# IMU.net
KiCad netlist of a schematic drawn in Altium Designer
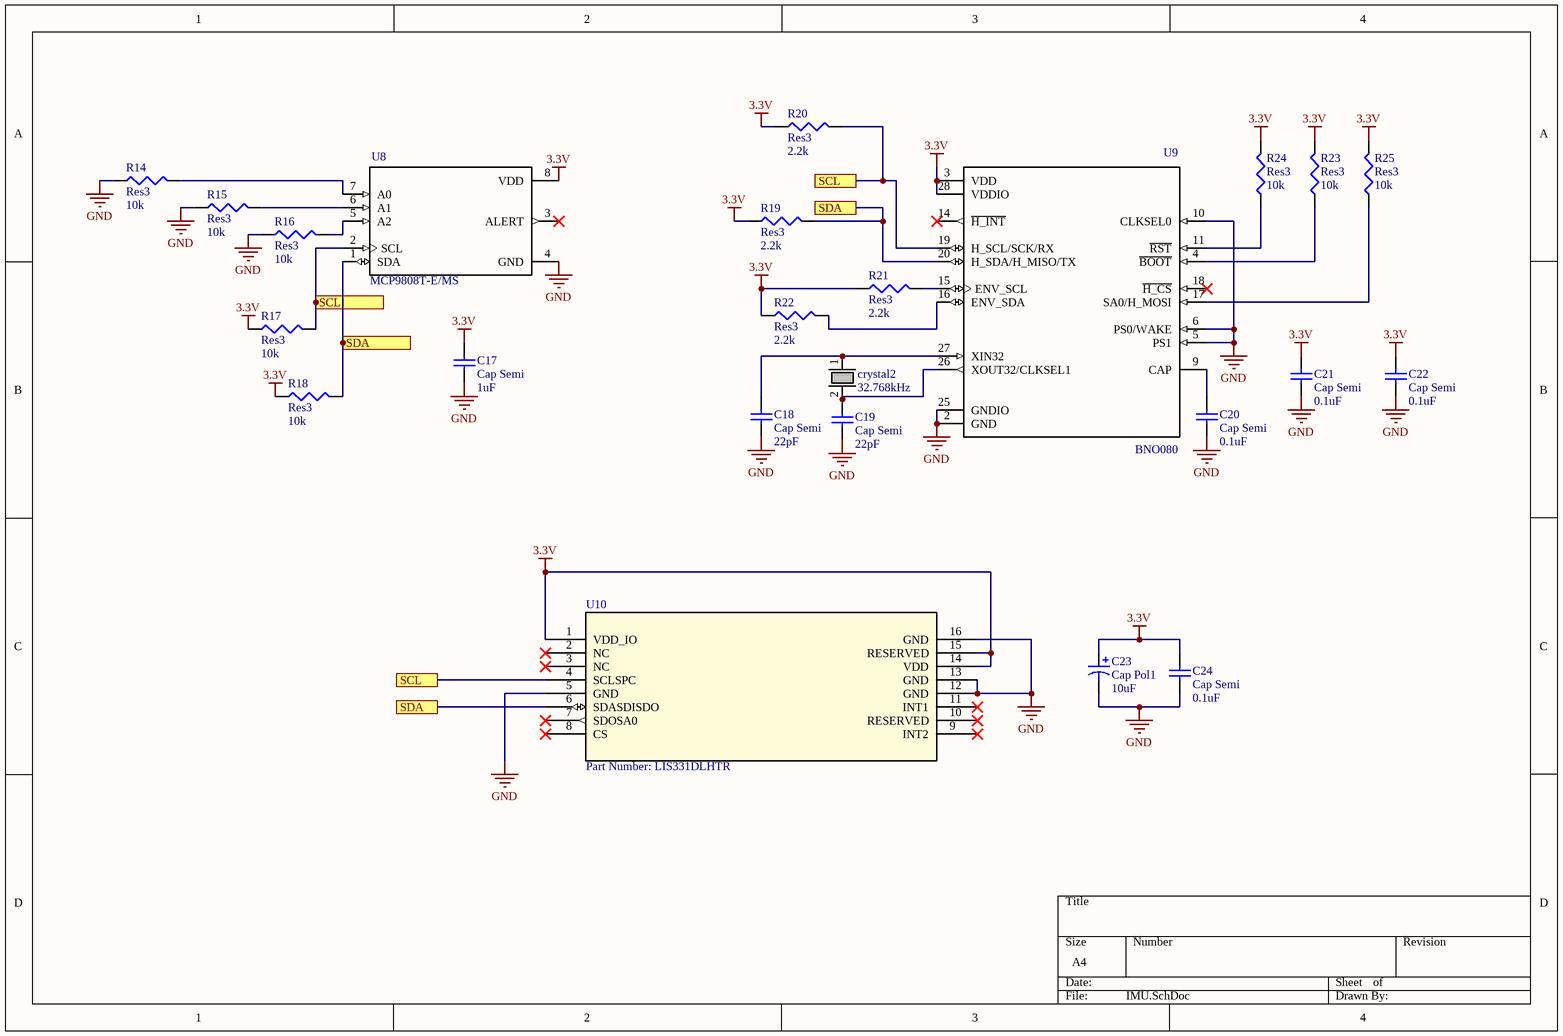
[diagram p0: IMU.SchDoc]

(export (version "E")
  (design (tool "Eeschema 10.0.6"))
  (components
    (comp (ref "C17")
      (value "Cap Semi")
      (footprint "C1206")
      (description "Capacitor (Semiconductor SIM Model)")
      (fields (field (name "ALTIUM_VALUE") "1uF") (field (name "PUBLISHER") "Altium Limited"))
      (libsource (lib "Miscellaneous Devices") (part "Cap Semi"))
    )
    (comp (ref "C18")
      (value "Cap Semi")
      (footprint "C1206")
      (description "Capacitor (Semiconductor SIM Model)")
      (fields (field (name "ALTIUM_VALUE") "22pF") (field (name "PUBLISHER") "Altium Limited"))
      (libsource (lib "Miscellaneous Devices") (part "Cap Semi"))
    )
    (comp (ref "C19")
      (value "Cap Semi")
      (footprint "C1206")
      (description "Capacitor (Semiconductor SIM Model)")
      (fields (field (name "ALTIUM_VALUE") "22pF") (field (name "PUBLISHER") "Altium Limited"))
      (libsource (lib "Miscellaneous Devices") (part "Cap Semi"))
    )
    (comp (ref "C20")
      (value "Cap Semi")
      (footprint "C1206")
      (description "Capacitor (Semiconductor SIM Model)")
      (fields (field (name "ALTIUM_VALUE") "0.1uF") (field (name "PUBLISHER") "Altium Limited"))
      (libsource (lib "Miscellaneous Devices") (part "Cap Semi"))
    )
    (comp (ref "C21")
      (value "Cap Semi")
      (footprint "C1206")
      (description "Capacitor (Semiconductor SIM Model)")
      (fields (field (name "ALTIUM_VALUE") "0.1uF") (field (name "PUBLISHER") "Altium Limited"))
      (libsource (lib "Miscellaneous Devices") (part "Cap Semi"))
    )
    (comp (ref "C22")
      (value "Cap Semi")
      (footprint "C1206")
      (description "Capacitor (Semiconductor SIM Model)")
      (fields (field (name "ALTIUM_VALUE") "0.1uF") (field (name "PUBLISHER") "Altium Limited"))
      (libsource (lib "Miscellaneous Devices") (part "Cap Semi"))
    )
    (comp (ref "C23")
      (value "Cap Pol1")
      (footprint "C1206")
      (description "Polarized Capacitor (Radial)")
      (fields (field (name "ALTIUM_VALUE") "10uF") (field (name "PUBLISHER") "Altium Limited"))
      (libsource (lib "Miscellaneous Devices") (part "Cap Pol1"))
    )
    (comp (ref "C24")
      (value "Cap Semi")
      (footprint "C1206")
      (description "Capacitor (Semiconductor SIM Model)")
      (fields (field (name "ALTIUM_VALUE") "0.1uF") (field (name "PUBLISHER") "Altium Limited"))
      (libsource (lib "Miscellaneous Devices") (part "Cap Semi"))
    )
    (comp (ref "crystal2")
      (value "32.768kHz")
      (footprint "ECS-.327-CDX-1128")
      (fields (field (name "Comment") "SMD_Crystal"))
      (libsource (lib "ECS-.327-CDX-1128") (part "ECS-.327-CDX-1128"))
    )
    (comp (ref "R14")
      (value "Res3")
      (footprint "6-0805_L")
      (description "Resistor")
      (fields (field (name "ALTIUM_VALUE") "10k") (field (name "PUBLISHER") "Altium Limited"))
      (libsource (lib "Miscellaneous Devices") (part "Res3"))
    )
    (comp (ref "R15")
      (value "Res3")
      (footprint "6-0805_L")
      (description "Resistor")
      (fields (field (name "ALTIUM_VALUE") "10k") (field (name "PUBLISHER") "Altium Limited"))
      (libsource (lib "Miscellaneous Devices") (part "Res3"))
    )
    (comp (ref "R16")
      (value "Res3")
      (footprint "6-0805_L")
      (description "Resistor")
      (fields (field (name "ALTIUM_VALUE") "10k") (field (name "PUBLISHER") "Altium Limited"))
      (libsource (lib "Miscellaneous Devices") (part "Res3"))
    )
    (comp (ref "R17")
      (value "Res3")
      (footprint "6-0805_L")
      (description "Resistor")
      (fields (field (name "ALTIUM_VALUE") "10k") (field (name "PUBLISHER") "Altium Limited"))
      (libsource (lib "Miscellaneous Devices") (part "Res3"))
    )
    (comp (ref "R18")
      (value "Res3")
      (footprint "6-0805_L")
      (description "Resistor")
      (fields (field (name "ALTIUM_VALUE") "10k") (field (name "PUBLISHER") "Altium Limited"))
      (libsource (lib "Miscellaneous Devices") (part "Res3"))
    )
    (comp (ref "R19")
      (value "Res3")
      (footprint "6-0805_L")
      (description "Resistor")
      (fields (field (name "ALTIUM_VALUE") "2.2k") (field (name "PUBLISHER") "Altium Limited"))
      (libsource (lib "Miscellaneous Devices") (part "Res3"))
    )
    (comp (ref "R20")
      (value "Res3")
      (footprint "6-0805_L")
      (description "Resistor")
      (fields (field (name "ALTIUM_VALUE") "2.2k") (field (name "PUBLISHER") "Altium Limited"))
      (libsource (lib "Miscellaneous Devices") (part "Res3"))
    )
    (comp (ref "R21")
      (value "Res3")
      (footprint "6-0805_L")
      (description "Resistor")
      (fields (field (name "ALTIUM_VALUE") "2.2k") (field (name "PUBLISHER") "Altium Limited"))
      (libsource (lib "Miscellaneous Devices") (part "Res3"))
    )
    (comp (ref "R22")
      (value "Res3")
      (footprint "6-0805_L")
      (description "Resistor")
      (fields (field (name "ALTIUM_VALUE") "2.2k") (field (name "PUBLISHER") "Altium Limited"))
      (libsource (lib "Miscellaneous Devices") (part "Res3"))
    )
    (comp (ref "R23")
      (value "Res3")
      (footprint "6-0805_L")
      (description "Resistor")
      (fields (field (name "ALTIUM_VALUE") "10k") (field (name "PUBLISHER") "Altium Limited"))
      (libsource (lib "Miscellaneous Devices") (part "Res3"))
    )
    (comp (ref "R24")
      (value "Res3")
      (footprint "6-0805_L")
      (description "Resistor")
      (fields (field (name "ALTIUM_VALUE") "10k") (field (name "PUBLISHER") "Altium Limited"))
      (libsource (lib "Miscellaneous Devices") (part "Res3"))
    )
    (comp (ref "R25")
      (value "Res3")
      (footprint "6-0805_L")
      (description "Resistor")
      (fields (field (name "ALTIUM_VALUE") "10k") (field (name "PUBLISHER") "Altium Limited"))
      (libsource (lib "Miscellaneous Devices") (part "Res3"))
    )
    (comp (ref "U8")
      (value "MCP9808T-E/MS")
      (footprint "*SOP65P490X110-8N")
      (description "MCP9808 Series 3.6 V Memory Module Digital Temperature Sensor SMT - MSOP-8")
      (fields (field (name "MF") "Microchip"))
      (libsource (lib "MCP9808T-E_MS") (part "MCP9808T-E/MS"))
    )
    (comp (ref "U9")
      (value "BNO080")
      (footprint "*IC_BNO080")
      (description "Imu Accel/Gyro/Mag I2c 32bit")
      (fields (field (name "MF") "Hillcrest Laboratories,"))
      (libsource (lib "BNO080") (part "BNO080"))
    )
    (comp (ref "U10")
      (value "Part Number: LIS331DLHTR")
      (footprint "LGA-16_3x3x1mm-M")
      (description "No Description Available")
      (fields
        (field (name "MANUFACTURER_PART_NUMBER") "LIS331DLHTR")
        (field (name "COPYRIGHT") "Copyright (C) 2018 Accelerated Designs. All rights reserved")
      )
      (libsource (lib "LIS331DLHTR") (part "LIS331DLHTR"))
    )
  )
  (nets
    (net (code "1") (name "/SCL") (class "Default")
      (node (ref "R17") (pin "2") (pinfunction "2_2") (pintype "passive"))
      (node (ref "R20") (pin "2") (pinfunction "2_2") (pintype "passive"))
      (node (ref "U10") (pin "4") (pinfunction "SCLSPC_4") (pintype "passive"))
      (node (ref "U8") (pin "2") (pinfunction "SCL_2") (pintype "input"))
      (node (ref "U9") (pin "19") (pinfunction "H_SCL/SCK/RX_19") (pintype "bidirectional"))
    )
    (net (code "2") (name "/SDA") (class "Default")
      (node (ref "R18") (pin "2") (pinfunction "2_2") (pintype "passive"))
      (node (ref "R19") (pin "2") (pinfunction "2_2") (pintype "passive"))
      (node (ref "U10") (pin "6") (pinfunction "SDASDISDO_6") (pintype "bidirectional"))
      (node (ref "U8") (pin "1") (pinfunction "SDA_1") (pintype "bidirectional"))
      (node (ref "U9") (pin "20") (pinfunction "H_SDA/H_MISO/TX_20") (pintype "bidirectional"))
    )
    (net (code "3") (name "3.3V") (class "Default")
      (node (ref "C17") (pin "2") (pinfunction "2_2") (pintype "passive"))
      (node (ref "C21") (pin "2") (pinfunction "2_2") (pintype "passive"))
      (node (ref "C22") (pin "2") (pinfunction "2_2") (pintype "passive"))
      (node (ref "C23") (pin "1") (pinfunction "1_1") (pintype "passive"))
      (node (ref "C24") (pin "2") (pinfunction "2_2") (pintype "passive"))
      (node (ref "R17") (pin "1") (pinfunction "1_1") (pintype "passive"))
      (node (ref "R18") (pin "1") (pinfunction "1_1") (pintype "passive"))
      (node (ref "R19") (pin "1") (pinfunction "1_1") (pintype "passive"))
      (node (ref "R20") (pin "1") (pinfunction "1_1") (pintype "passive"))
      (node (ref "R21") (pin "1") (pinfunction "1_1") (pintype "passive"))
      (node (ref "R22") (pin "1") (pinfunction "1_1") (pintype "passive"))
      (node (ref "R23") (pin "2") (pinfunction "2_2") (pintype "passive"))
      (node (ref "R24") (pin "2") (pinfunction "2_2") (pintype "passive"))
      (node (ref "R25") (pin "2") (pinfunction "2_2") (pintype "passive"))
      (node (ref "U10") (pin "1") (pinfunction "VDD_IO_1") (pintype "power_in"))
      (node (ref "U10") (pin "14") (pinfunction "VDD_14") (pintype "power_in"))
      (node (ref "U10") (pin "15") (pinfunction "RESERVED_15") (pintype "passive"))
      (node (ref "U8") (pin "8") (pinfunction "VDD_8") (pintype "power_in"))
      (node (ref "U9") (pin "28") (pinfunction "VDDIO_28") (pintype "power_in"))
      (node (ref "U9") (pin "3") (pinfunction "VDD_3") (pintype "power_in"))
    )
    (net (code "4") (name "GND") (class "Default")
      (node (ref "C17") (pin "1") (pinfunction "1_1") (pintype "passive"))
      (node (ref "C18") (pin "1") (pinfunction "1_1") (pintype "passive"))
      (node (ref "C19") (pin "1") (pinfunction "1_1") (pintype "passive"))
      (node (ref "C20") (pin "1") (pinfunction "1_1") (pintype "passive"))
      (node (ref "C21") (pin "1") (pinfunction "1_1") (pintype "passive"))
      (node (ref "C22") (pin "1") (pinfunction "1_1") (pintype "passive"))
      (node (ref "C23") (pin "2") (pinfunction "2_2") (pintype "passive"))
      (node (ref "C24") (pin "1") (pinfunction "1_1") (pintype "passive"))
      (node (ref "R14") (pin "1") (pinfunction "1_1") (pintype "passive"))
      (node (ref "R15") (pin "1") (pinfunction "1_1") (pintype "passive"))
      (node (ref "R16") (pin "1") (pinfunction "1_1") (pintype "passive"))
      (node (ref "U10") (pin "12") (pinfunction "GND_12") (pintype "power_in"))
      (node (ref "U10") (pin "13") (pinfunction "GND_13") (pintype "power_in"))
      (node (ref "U10") (pin "16") (pinfunction "GND_16") (pintype "power_in"))
      (node (ref "U10") (pin "5") (pinfunction "GND_5") (pintype "power_in"))
      (node (ref "U8") (pin "4") (pinfunction "GND_4") (pintype "power_in"))
      (node (ref "U9") (pin "10") (pinfunction "CLKSEL0_10") (pintype "input"))
      (node (ref "U9") (pin "2") (pinfunction "GND_2") (pintype "power_in"))
      (node (ref "U9") (pin "25") (pinfunction "GNDIO_25") (pintype "power_in"))
      (node (ref "U9") (pin "5") (pinfunction "PS1_5") (pintype "input"))
      (node (ref "U9") (pin "6") (pinfunction "PS0/WAKE_6") (pintype "input"))
    )
    (net (code "5") (name "Net-(U8-A0)") (class "Default")
      (node (ref "R14") (pin "2") (pinfunction "2_2") (pintype "passive"))
      (node (ref "U8") (pin "7") (pinfunction "A0_7") (pintype "input"))
    )
    (net (code "6") (name "Net-(U8-A1)") (class "Default")
      (node (ref "R15") (pin "2") (pinfunction "2_2") (pintype "passive"))
      (node (ref "U8") (pin "6") (pinfunction "A1_6") (pintype "input"))
    )
    (net (code "7") (name "Net-(U8-A2)") (class "Default")
      (node (ref "R16") (pin "2") (pinfunction "2_2") (pintype "passive"))
      (node (ref "U8") (pin "5") (pinfunction "A2_5") (pintype "input"))
    )
    (net (code "8") (name "Net-(U9-CAP)") (class "Default")
      (node (ref "C20") (pin "2") (pinfunction "2_2") (pintype "passive"))
      (node (ref "U9") (pin "9") (pinfunction "CAP_9") (pintype "passive"))
    )
    (net (code "9") (name "Net-(U9-ENV_SCL)") (class "Default")
      (node (ref "R21") (pin "2") (pinfunction "2_2") (pintype "passive"))
      (node (ref "U9") (pin "15") (pinfunction "ENV_SCL_15") (pintype "bidirectional"))
    )
    (net (code "10") (name "Net-(U9-ENV_SDA)") (class "Default")
      (node (ref "R22") (pin "2") (pinfunction "2_2") (pintype "passive"))
      (node (ref "U9") (pin "16") (pinfunction "ENV_SDA_16") (pintype "bidirectional"))
    )
    (net (code "11") (name "Net-(U9-SA0{slash}H_MOSI)") (class "Default")
      (node (ref "R25") (pin "1") (pinfunction "1_1") (pintype "passive"))
      (node (ref "U9") (pin "17") (pinfunction "SA0/H_MOSI_17") (pintype "input"))
    )
    (net (code "12") (name "Net-(U9-XIN32)") (class "Default")
      (node (ref "C18") (pin "2") (pinfunction "2_2") (pintype "passive"))
      (node (ref "U9") (pin "27") (pinfunction "XIN32_27") (pintype "input"))
      (node (ref "crystal2") (pin "1") (pinfunction "1_1") (pintype "passive"))
    )
    (net (code "13") (name "Net-(U9-XOUT32{slash}CLKSEL1)") (class "Default")
      (node (ref "C19") (pin "2") (pinfunction "2_2") (pintype "passive"))
      (node (ref "U9") (pin "26") (pinfunction "XOUT32/CLKSEL1_26") (pintype "output"))
      (node (ref "crystal2") (pin "2") (pinfunction "2_2") (pintype "passive"))
    )
    (net (code "14") (name "Net-(U9-~{BOOT})") (class "Default")
      (node (ref "R23") (pin "1") (pinfunction "1_1") (pintype "passive"))
      (node (ref "U9") (pin "4") (pinfunction "~{BOOT}_4") (pintype "input"))
    )
    (net (code "15") (name "Net-(U9-~{RST})") (class "Default")
      (node (ref "R24") (pin "1") (pinfunction "1_1") (pintype "passive"))
      (node (ref "U9") (pin "11") (pinfunction "~{RST}_11") (pintype "input"))
    )
    (net (code "16") (name "unconnected-(U8-ALERT-Pad3)") (class "Default")
      (node (ref "U8") (pin "3") (pinfunction "ALERT_3") (pintype "output+no_connect"))
    )
    (net (code "17") (name "unconnected-(U9-~{H_CS}-Pad18)") (class "Default")
      (node (ref "U9") (pin "18") (pinfunction "~{H_CS}_18") (pintype "input+no_connect"))
    )
    (net (code "18") (name "unconnected-(U9-~{H_INT}-Pad14)") (class "Default")
      (node (ref "U9") (pin "14") (pinfunction "~{H_INT}_14") (pintype "output+no_connect"))
    )
    (net (code "19") (name "unconnected-(U10-CS-Pad8)") (class "Default")
      (node (ref "U10") (pin "8") (pinfunction "CS_8") (pintype "passive+no_connect"))
    )
    (net (code "20") (name "unconnected-(U10-INT1-Pad11)") (class "Default")
      (node (ref "U10") (pin "11") (pinfunction "INT1_11") (pintype "passive+no_connect"))
    )
    (net (code "21") (name "unconnected-(U10-INT2-Pad9)") (class "Default")
      (node (ref "U10") (pin "9") (pinfunction "INT2_9") (pintype "passive+no_connect"))
    )
    (net (code "22") (name "unconnected-(U10-NC-Pad2)") (class "Default")
      (node (ref "U10") (pin "2") (pinfunction "NC_2") (pintype "passive+no_connect"))
    )
    (net (code "23") (name "unconnected-(U10-NC-Pad3)") (class "Default")
      (node (ref "U10") (pin "3") (pinfunction "NC_3") (pintype "passive+no_connect"))
    )
    (net (code "24") (name "unconnected-(U10-RESERVED-Pad10)") (class "Default")
      (node (ref "U10") (pin "10") (pinfunction "RESERVED_10") (pintype "passive+no_connect"))
    )
    (net (code "25") (name "unconnected-(U10-SDOSA0-Pad7)") (class "Default")
      (node (ref "U10") (pin "7") (pinfunction "SDOSA0_7") (pintype "output+no_connect"))
    )
  )
)
